# v5-CPU-Section-temp.net
KiCad netlist of a schematic drawn in EAGLE
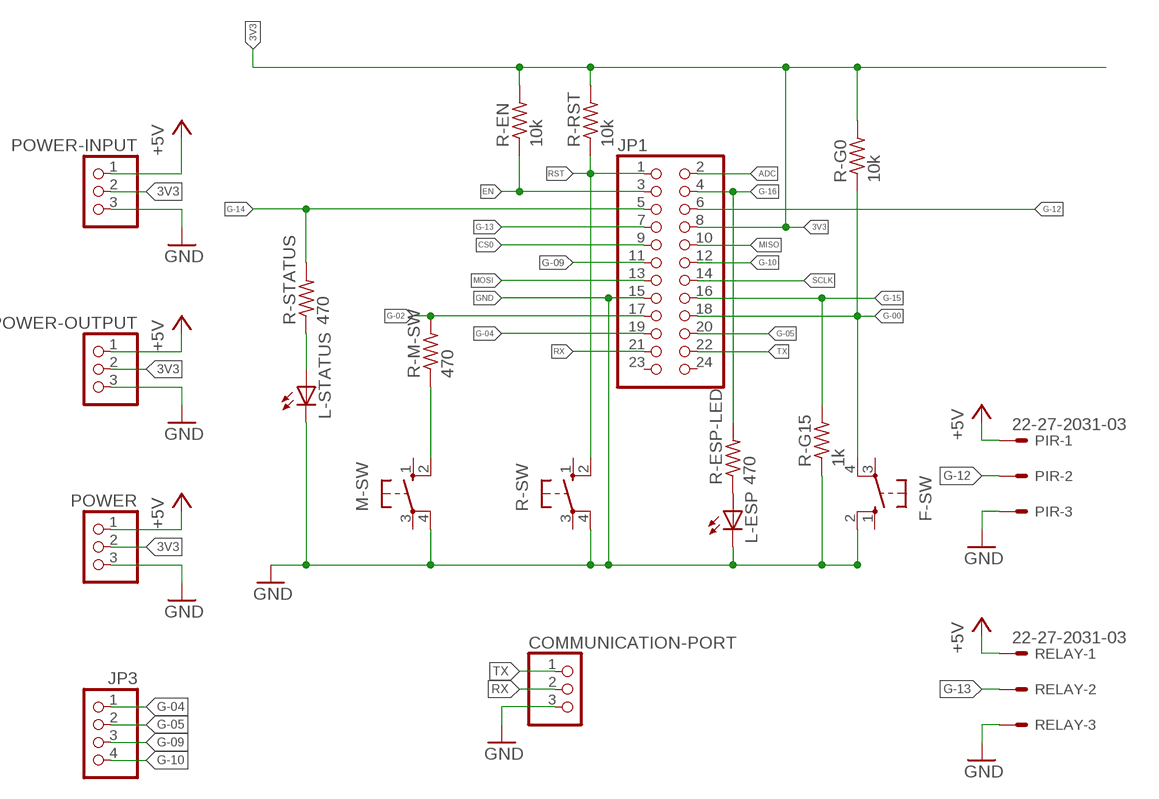
[diagram p0: schematic, sheet 1]

(export (version "E")
  (design (tool "Eeschema 10.0.6"))
  (components
    (comp (ref "COMMUNICATION-PORT")
      (value "PINHD-1X3")
      (footprint "eagle-import:1X03")
      (libsource (lib "eagle-import") (part "PINHD-1X3"))
    )
    (comp (ref "F-SW")
      (value "10-XX")
      (footprint "eagle-import:B3F-10XX")
      (fields (field (name "MPN") "B3F-1000"))
      (libsource (lib "eagle-import") (part "10-XX"))
    )
    (comp (ref "JP1")
      (value "PINHD-2X12")
      (footprint "eagle-import:2X12")
      (libsource (lib "eagle-import") (part "PINHD-2X12"))
    )
    (comp (ref "JP3")
      (value "PINHD-1X4")
      (footprint "eagle-import:1X04")
      (libsource (lib "eagle-import") (part "PINHD-1X4"))
    )
    (comp (ref "L-ESP")
      (value "LED3MM")
      (footprint "eagle-import:LED3MM")
      (libsource (lib "eagle-import") (part "LED3MM"))
    )
    (comp (ref "L-STATUS")
      (value "LED3MM")
      (footprint "eagle-import:LED3MM")
      (libsource (lib "eagle-import") (part "LED3MM"))
    )
    (comp (ref "M-SW")
      (value "10-XX")
      (footprint "eagle-import:B3F-10XX")
      (fields (field (name "MPN") "B3F-1000"))
      (libsource (lib "eagle-import") (part "10-XX"))
    )
    (comp (ref "PIR")
      (value "22-27-2031-03")
      (footprint "eagle-import:6410-03")
      (libsource (lib "eagle-import") (part "22-?-0327-2031"))
    )
    (comp (ref "POWER")
      (value "PINHD-1X3")
      (footprint "eagle-import:1X03")
      (libsource (lib "eagle-import") (part "PINHD-1X3"))
    )
    (comp (ref "POWER-INPUT")
      (value "PINHD-1X3")
      (footprint "eagle-import:1X03")
      (libsource (lib "eagle-import") (part "PINHD-1X3"))
    )
    (comp (ref "POWER-OUTPUT")
      (value "PINHD-1X3")
      (footprint "eagle-import:1X03")
      (libsource (lib "eagle-import") (part "PINHD-1X3"))
    )
    (comp (ref "R-EN")
      (value "10k")
      (footprint "eagle-import:0207_7")
      (libsource (lib "eagle-import") (part "R-US_0207/7"))
    )
    (comp (ref "R-ESP-LED")
      (value "470")
      (footprint "eagle-import:0207_7")
      (libsource (lib "eagle-import") (part "R-US_0207/7"))
    )
    (comp (ref "R-G0")
      (value "10k")
      (footprint "eagle-import:0207_7")
      (libsource (lib "eagle-import") (part "R-US_0207/7"))
    )
    (comp (ref "R-G15")
      (value "1k")
      (footprint "eagle-import:0207_7")
      (libsource (lib "eagle-import") (part "R-US_0207/7"))
    )
    (comp (ref "R-M-SW")
      (value "470")
      (footprint "eagle-import:0207_7")
      (libsource (lib "eagle-import") (part "R-US_0207/7"))
    )
    (comp (ref "R-RST")
      (value "10k")
      (footprint "eagle-import:0207_7")
      (libsource (lib "eagle-import") (part "R-US_0207/7"))
    )
    (comp (ref "R-STATUS")
      (value "470")
      (footprint "eagle-import:0207_7")
      (libsource (lib "eagle-import") (part "R-US_0207/7"))
    )
    (comp (ref "R-SW")
      (value "10-XX")
      (footprint "eagle-import:B3F-10XX")
      (fields (field (name "MPN") "B3F-1000"))
      (libsource (lib "eagle-import") (part "10-XX"))
    )
    (comp (ref "RELAY")
      (value "22-27-2031-03")
      (footprint "eagle-import:6410-03")
      (libsource (lib "eagle-import") (part "22-?-0327-2031"))
    )
  )
  (nets
    (net (code "1") (name "+5V") (class "Default")
      (node (ref "PIR") (pin "1") (pinfunction "S_1") (pintype "passive"))
      (node (ref "POWER") (pin "1") (pinfunction "1_1") (pintype "passive"))
      (node (ref "POWER-INPUT") (pin "1") (pinfunction "1_1") (pintype "passive"))
      (node (ref "POWER-OUTPUT") (pin "1") (pinfunction "1_1") (pintype "passive"))
      (node (ref "RELAY") (pin "1") (pinfunction "S_1") (pintype "passive"))
    )
    (net (code "2") (name "3V3") (class "Default")
      (node (ref "JP1") (pin "8") (pinfunction "8_8") (pintype "passive"))
      (node (ref "POWER") (pin "2") (pinfunction "2_2") (pintype "passive"))
      (node (ref "POWER-INPUT") (pin "2") (pinfunction "2_2") (pintype "passive"))
      (node (ref "POWER-OUTPUT") (pin "2") (pinfunction "2_2") (pintype "passive"))
      (node (ref "R-EN") (pin "2") (pinfunction "2_2") (pintype "passive"))
      (node (ref "R-G0") (pin "2") (pinfunction "2_2") (pintype "passive"))
      (node (ref "R-RST") (pin "2") (pinfunction "2_2") (pintype "passive"))
    )
    (net (code "3") (name "ADC") (class "Default")
      (node (ref "JP1") (pin "2") (pinfunction "2_2") (pintype "passive"))
    )
    (net (code "4") (name "CS0") (class "Default")
      (node (ref "JP1") (pin "9") (pinfunction "9_9") (pintype "passive"))
    )
    (net (code "5") (name "EN") (class "Default")
      (node (ref "JP1") (pin "3") (pinfunction "3_3") (pintype "passive"))
      (node (ref "R-EN") (pin "1") (pinfunction "1_1") (pintype "passive"))
    )
    (net (code "6") (name "G-00") (class "Default")
      (node (ref "F-SW") (pin "4") (pinfunction "P1_4") (pintype "passive"))
      (node (ref "JP1") (pin "18") (pinfunction "18_18") (pintype "passive"))
      (node (ref "R-G0") (pin "1") (pinfunction "1_1") (pintype "passive"))
    )
    (net (code "7") (name "G-02") (class "Default")
      (node (ref "JP1") (pin "17") (pinfunction "17_17") (pintype "passive"))
      (node (ref "R-M-SW") (pin "2") (pinfunction "2_2") (pintype "passive"))
    )
    (net (code "8") (name "G-04") (class "Default")
      (node (ref "JP1") (pin "19") (pinfunction "19_19") (pintype "passive"))
      (node (ref "JP3") (pin "1") (pinfunction "1_1") (pintype "passive"))
    )
    (net (code "9") (name "G-05") (class "Default")
      (node (ref "JP1") (pin "20") (pinfunction "20_20") (pintype "passive"))
      (node (ref "JP3") (pin "2") (pinfunction "2_2") (pintype "passive"))
    )
    (net (code "10") (name "G-09") (class "Default")
      (node (ref "JP1") (pin "11") (pinfunction "11_11") (pintype "passive"))
      (node (ref "JP3") (pin "3") (pinfunction "3_3") (pintype "passive"))
    )
    (net (code "11") (name "G-10") (class "Default")
      (node (ref "JP1") (pin "12") (pinfunction "12_12") (pintype "passive"))
      (node (ref "JP3") (pin "4") (pinfunction "4_4") (pintype "passive"))
    )
    (net (code "12") (name "G-12") (class "Default")
      (node (ref "JP1") (pin "6") (pinfunction "6_6") (pintype "passive"))
      (node (ref "PIR") (pin "2") (pinfunction "S_2") (pintype "passive"))
    )
    (net (code "13") (name "G-13") (class "Default")
      (node (ref "JP1") (pin "7") (pinfunction "7_7") (pintype "passive"))
      (node (ref "RELAY") (pin "2") (pinfunction "S_2") (pintype "passive"))
    )
    (net (code "14") (name "G-14") (class "Default")
      (node (ref "JP1") (pin "5") (pinfunction "5_5") (pintype "passive"))
      (node (ref "R-STATUS") (pin "2") (pinfunction "2_2") (pintype "passive"))
    )
    (net (code "15") (name "G-15") (class "Default")
      (node (ref "JP1") (pin "16") (pinfunction "16_16") (pintype "passive"))
      (node (ref "R-G15") (pin "2") (pinfunction "2_2") (pintype "passive"))
    )
    (net (code "16") (name "G-16") (class "Default")
      (node (ref "JP1") (pin "4") (pinfunction "4_4") (pintype "passive"))
      (node (ref "R-ESP-LED") (pin "2") (pinfunction "2_2") (pintype "passive"))
    )
    (net (code "17") (name "GND") (class "Default")
      (node (ref "COMMUNICATION-PORT") (pin "3") (pinfunction "3_3") (pintype "passive"))
      (node (ref "F-SW") (pin "2") (pinfunction "S1_2") (pintype "passive"))
      (node (ref "JP1") (pin "15") (pinfunction "15_15") (pintype "passive"))
      (node (ref "L-ESP") (pin "K") (pinfunction "C_K") (pintype "passive"))
      (node (ref "L-STATUS") (pin "K") (pinfunction "C_K") (pintype "passive"))
      (node (ref "M-SW") (pin "4") (pinfunction "P1_4") (pintype "passive"))
      (node (ref "PIR") (pin "3") (pinfunction "S_3") (pintype "passive"))
      (node (ref "POWER") (pin "3") (pinfunction "3_3") (pintype "passive"))
      (node (ref "POWER-INPUT") (pin "3") (pinfunction "3_3") (pintype "passive"))
      (node (ref "POWER-OUTPUT") (pin "3") (pinfunction "3_3") (pintype "passive"))
      (node (ref "R-G15") (pin "1") (pinfunction "1_1") (pintype "passive"))
      (node (ref "R-SW") (pin "4") (pinfunction "P1_4") (pintype "passive"))
      (node (ref "RELAY") (pin "3") (pinfunction "S_3") (pintype "passive"))
    )
    (net (code "18") (name "MISO") (class "Default")
      (node (ref "JP1") (pin "10") (pinfunction "10_10") (pintype "passive"))
    )
    (net (code "19") (name "MOSI") (class "Default")
      (node (ref "JP1") (pin "13") (pinfunction "13_13") (pintype "passive"))
    )
    (net (code "20") (name "Net-(L-ESP-PadA)") (class "Default")
      (node (ref "L-ESP") (pin "A") (pinfunction "A_A") (pintype "passive"))
      (node (ref "R-ESP-LED") (pin "1") (pinfunction "1_1") (pintype "passive"))
    )
    (net (code "21") (name "Net-(L-STATUS-PadA)") (class "Default")
      (node (ref "L-STATUS") (pin "A") (pinfunction "A_A") (pintype "passive"))
      (node (ref "R-STATUS") (pin "1") (pinfunction "1_1") (pintype "passive"))
    )
    (net (code "22") (name "Net-(M-SW-S1)") (class "Default")
      (node (ref "M-SW") (pin "2") (pinfunction "S1_2") (pintype "passive"))
      (node (ref "R-M-SW") (pin "1") (pinfunction "1_1") (pintype "passive"))
    )
    (net (code "23") (name "RST") (class "Default")
      (node (ref "JP1") (pin "1") (pinfunction "1_1") (pintype "passive"))
      (node (ref "R-RST") (pin "1") (pinfunction "1_1") (pintype "passive"))
      (node (ref "R-SW") (pin "2") (pinfunction "S1_2") (pintype "passive"))
    )
    (net (code "24") (name "RX") (class "Default")
      (node (ref "COMMUNICATION-PORT") (pin "2") (pinfunction "2_2") (pintype "passive"))
      (node (ref "JP1") (pin "21") (pinfunction "21_21") (pintype "passive"))
    )
    (net (code "25") (name "SCLK") (class "Default")
      (node (ref "JP1") (pin "14") (pinfunction "14_14") (pintype "passive"))
    )
    (net (code "26") (name "TX") (class "Default")
      (node (ref "COMMUNICATION-PORT") (pin "1") (pinfunction "1_1") (pintype "passive"))
      (node (ref "JP1") (pin "22") (pinfunction "22_22") (pintype "passive"))
    )
    (net (code "27") (name "unconnected-(F-SW-P-Pad3)") (class "Default")
      (node (ref "F-SW") (pin "3") (pinfunction "P_3") (pintype "passive"))
    )
    (net (code "28") (name "unconnected-(F-SW-S-Pad1)") (class "Default")
      (node (ref "F-SW") (pin "1") (pinfunction "S_1") (pintype "passive"))
    )
    (net (code "29") (name "unconnected-(JP1-Pad23)") (class "Default")
      (node (ref "JP1") (pin "23") (pinfunction "23_23") (pintype "passive"))
    )
    (net (code "30") (name "unconnected-(JP1-Pad24)") (class "Default")
      (node (ref "JP1") (pin "24") (pinfunction "24_24") (pintype "passive"))
    )
    (net (code "31") (name "unconnected-(M-SW-P-Pad3)") (class "Default")
      (node (ref "M-SW") (pin "3") (pinfunction "P_3") (pintype "passive"))
    )
    (net (code "32") (name "unconnected-(M-SW-S-Pad1)") (class "Default")
      (node (ref "M-SW") (pin "1") (pinfunction "S_1") (pintype "passive"))
    )
    (net (code "33") (name "unconnected-(R-SW-P-Pad3)") (class "Default")
      (node (ref "R-SW") (pin "3") (pinfunction "P_3") (pintype "passive"))
    )
    (net (code "34") (name "unconnected-(R-SW-S-Pad1)") (class "Default")
      (node (ref "R-SW") (pin "1") (pinfunction "S_1") (pintype "passive"))
    )
  )
)
